# Dispaly.net
KiCad netlist of a schematic drawn in Altium Designer
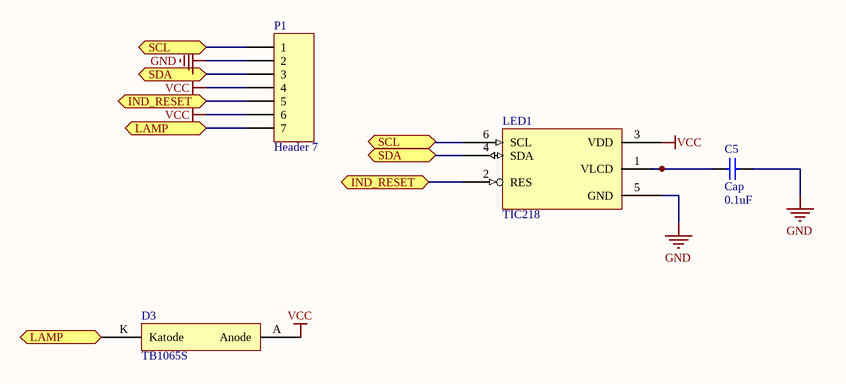
[diagram p0: Dispaly.SchDoc]

(export (version "E")
  (design (tool "Eeschema 10.0.6"))
  (components
    (comp (ref "C5")
      (value "Cap")
      (footprint "CAPC3225L")
      (description "Capacitor")
      (fields (field (name "ALTIUM_VALUE") "0.1uF") (field (name "PUBLISHER") "Altium Limited"))
      (libsource (lib "Miscellaneous Devices") (part "Cap"))
    )
    (comp (ref "D3")
      (value "TB1065S")
      (footprint "TB1065S")
      (description "Подсветка диодна  дл  индикатора TIC218")
      (libsource (lib "Gamma IND") (part "TB1065S"))
    )
    (comp (ref "LED1") (value "TIC218") (footprint "TIC218") (libsource (lib "Gamma IND") (part "TIC218")))
    (comp (ref "P1")
      (value "Header 7")
      (footprint "HDR1X7")
      (description "Header, 7-Pin")
      (fields (field (name "PUBLISHER") "Altium Limited"))
      (libsource (lib "Miscellaneous Connectors") (part "Header 7"))
    )
  )
  (nets
    (net (code "1") (name "/IND_RESET") (class "Default")
      (node (ref "LED1") (pin "2") (pinfunction "RES_2") (pintype "input"))
      (node (ref "P1") (pin "5") (pinfunction "5_5") (pintype "passive"))
    )
    (net (code "2") (name "/LAMP") (class "Default")
      (node (ref "D3") (pin "K") (pinfunction "Katode_K") (pintype "passive"))
      (node (ref "P1") (pin "7") (pinfunction "7_7") (pintype "passive"))
    )
    (net (code "3") (name "/SCL") (class "Default")
      (node (ref "LED1") (pin "6") (pinfunction "SCL_6") (pintype "input"))
      (node (ref "P1") (pin "1") (pinfunction "1_1") (pintype "passive"))
    )
    (net (code "4") (name "/SDA") (class "Default")
      (node (ref "LED1") (pin "4") (pinfunction "SDA_4") (pintype "bidirectional"))
      (node (ref "P1") (pin "3") (pinfunction "3_3") (pintype "passive"))
    )
    (net (code "5") (name "GND") (class "Default")
      (node (ref "C5") (pin "2") (pinfunction "2_2") (pintype "passive"))
      (node (ref "LED1") (pin "5") (pinfunction "GND_5") (pintype "passive"))
      (node (ref "LED1") (pin "7") (pinfunction "GND_7") (pintype "power_in"))
      (node (ref "P1") (pin "2") (pinfunction "2_2") (pintype "passive"))
    )
    (net (code "6") (name "Net-(LED1-VLCD)") (class "Default")
      (node (ref "C5") (pin "1") (pinfunction "1_1") (pintype "passive"))
      (node (ref "LED1") (pin "1") (pinfunction "VLCD_1") (pintype "passive"))
    )
    (net (code "7") (name "VCC") (class "Default")
      (node (ref "D3") (pin "A") (pinfunction "Anode_A") (pintype "passive"))
      (node (ref "LED1") (pin "3") (pinfunction "VDD_3") (pintype "passive"))
      (node (ref "P1") (pin "4") (pinfunction "4_4") (pintype "passive"))
      (node (ref "P1") (pin "6") (pinfunction "6_6") (pintype "passive"))
    )
  )
)
